# BOOST.net
KiCad netlist of a schematic drawn in Altium Designer
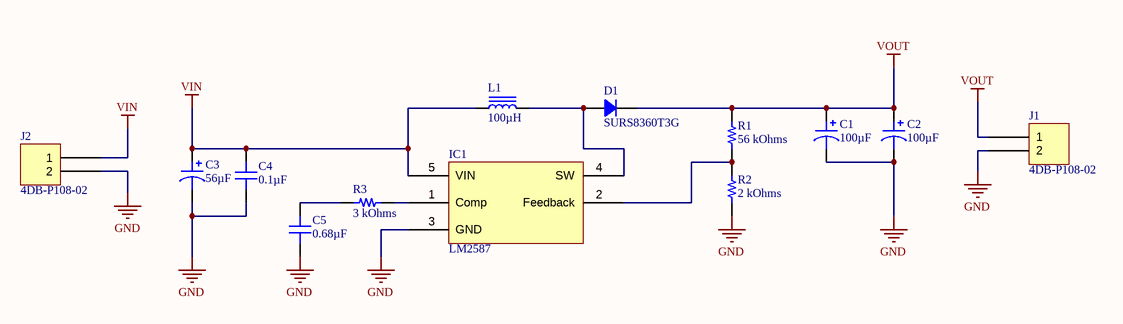
[diagram p0: BOOST.SchDoc]

(export (version "E")
  (design (tool "Eeschema 10.0.6"))
  (components
    (comp (ref "C1")
      (value "100µF")
      (footprint "CAP ALSMD 8.3MM H10.5MM")
      (description "CAP ALUM 100UF 20% 50V SMD")
      (fields
        (field (name "PART NUMBER") "EEE-FK1H101P")
        (field (name "MANUFACTURER") "Panasonic Electronic Components")
      )
      (libsource (lib "Celestial Altium Library - altium_library") (part "Polarised Capacitor"))
    )
    (comp (ref "C2")
      (value "100µF")
      (footprint "CAP ALSMD 8.3MM H10.5MM")
      (description "CAP ALUM 100UF 20% 50V SMD")
      (fields
        (field (name "PART NUMBER") "EEE-FK1H101P")
        (field (name "MANUFACTURER") "Panasonic Electronic Components")
      )
      (libsource (lib "Celestial Altium Library - altium_library") (part "Polarised Capacitor"))
    )
    (comp (ref "C3")
      (value "56µF")
      (footprint "CAP ALSMD 6.6MM H7.7MM")
      (description "CAP ALUM 56UF 20% 35V SMD")
      (fields (field (name "PART NUMBER") "UWD1V560MCL1GS") (field (name "MANUFACTURER") "Nichicon"))
      (libsource (lib "Celestial Altium Library - altium_library") (part "Polarised Capacitor"))
    )
    (comp (ref "C4")
      (value "0.1µF")
      (footprint "CAP 0805_2012")
      (description "CAP CER 0.1UF 50V X7R 0805")
      (fields (field (name "PART NUMBER") "CC0805JRX7R9BB104") (field (name "MANUFACTURER") "Yageo"))
      (libsource (lib "Celestial Altium Library - altium_library") (part "Capacitor"))
    )
    (comp (ref "C5")
      (value "0.68µF")
      (footprint "CAP 0805_2012")
      (description "CAP CER 0.68UF 50V X7R 0805")
      (fields (field (name "PART NUMBER") "C0805C684K5RACTU") (field (name "MANUFACTURER") "KEMET"))
      (libsource (lib "Celestial Altium Library - altium_library") (part "Capacitor"))
    )
    (comp (ref "D1")
      (value "SURS8360T3G")
      (footprint "DO214AB SMC")
      (description "DIODE GEN PURP 600V 3A SMC")
      (fields (field (name "MANUFACTURER") "ON Semiconductor"))
      (libsource (lib "Celestial Altium Library - altium_library") (part "Diode"))
    )
    (comp (ref "IC1")
      (value "LM2587")
      (footprint "AltiumLive:D2PAK")
      (description "Boost Converter")
      (libsource (lib "AltiumLive") (part "LM2587"))
    )
    (comp (ref "J1")
      (value "4DB-P108-02")
      (footprint "TE 4DB-P108-02")
      (description "CONN BARRIER STRIP 2CIRC 0.325\"")
      (fields (field (name "MANUFACTURER") "TE Connectivity AMP Connectors"))
      (libsource (lib "") (part "2 Pin_1"))
    )
    (comp (ref "J2")
      (value "4DB-P108-02")
      (footprint "TE 4DB-P108-02")
      (description "CONN BARRIER STRIP 2CIRC 0.325\"")
      (fields (field (name "MANUFACTURER") "TE Connectivity AMP Connectors"))
      (libsource (lib "Celestial Altium Library - altium_library") (part "2 Pin"))
    )
    (comp (ref "L1")
      (value "100µH")
      (footprint "AltiumLive:7447070")
      (description "FIXED IND 100UH 2.1A 150MOHM SMD")
      (fields (field (name "PART NUMBER") "SRR1280-101M") (field (name "MANUFACTURER") "Bourns Inc."))
      (libsource (lib "Celestial Altium Library - altium_library") (part "Inductor"))
    )
    (comp (ref "R1")
      (value "56 kOhms")
      (footprint "RES 0805_2012")
      (description "RES 56K OHM 1% 1/8W 0805")
      (fields
        (field (name "PART NUMBER") "RMCF0805FT56K0")
        (field (name "MANUFACTURER") "Stackpole Electronics Inc")
      )
      (libsource (lib "Celestial Altium Library - altium_library") (part "Resistor"))
    )
    (comp (ref "R2")
      (value "2 kOhms")
      (footprint "RES 0805_2012")
      (description "RES SMD 2K OHM 1% 1/8W 0805")
      (fields (field (name "PART NUMBER") "AC0805FR-072KL") (field (name "MANUFACTURER") "Yageo"))
      (libsource (lib "Celestial Altium Library - altium_library") (part "Resistor"))
    )
    (comp (ref "R3")
      (value "3 kOhms")
      (footprint "RES 0805_2012")
      (description "RES SMD 3K OHM 1% 1/8W 0805")
      (fields
        (field (name "PART NUMBER") "ERJ-6ENF3001V")
        (field (name "MANUFACTURER") "Panasonic Electronic Components")
      )
      (libsource (lib "Celestial Altium Library - altium_library") (part "Resistor"))
    )
  )
  (nets
    (net (code "1") (name "GND") (class "Default")
      (node (ref "C1") (pin "2") (pinfunction "2_2") (pintype "passive"))
      (node (ref "C2") (pin "2") (pinfunction "2_2") (pintype "passive"))
      (node (ref "C3") (pin "2") (pinfunction "2_2") (pintype "passive"))
      (node (ref "C4") (pin "1") (pinfunction "1_1") (pintype "passive"))
      (node (ref "C5") (pin "1") (pinfunction "1_1") (pintype "passive"))
      (node (ref "IC1") (pin "3") (pinfunction "GND_3") (pintype "passive"))
      (node (ref "J1") (pin "2") (pinfunction "2_2") (pintype "passive"))
      (node (ref "J2") (pin "2") (pinfunction "2_2") (pintype "passive"))
      (node (ref "R2") (pin "1") (pinfunction "1_1") (pintype "passive"))
    )
    (net (code "2") (name "Net-(C5-Pad2)") (class "Default")
      (node (ref "C5") (pin "2") (pinfunction "2_2") (pintype "passive"))
      (node (ref "R3") (pin "2") (pinfunction "2_2") (pintype "passive"))
    )
    (net (code "3") (name "Net-(IC1-Comp)") (class "Default")
      (node (ref "IC1") (pin "1") (pinfunction "Comp_1") (pintype "passive"))
      (node (ref "R3") (pin "1") (pinfunction "1_1") (pintype "passive"))
    )
    (net (code "4") (name "Net-(IC1-Feedback)") (class "Default")
      (node (ref "IC1") (pin "2") (pinfunction "Feedback_2") (pintype "passive"))
      (node (ref "R1") (pin "1") (pinfunction "1_1") (pintype "passive"))
      (node (ref "R2") (pin "2") (pinfunction "2_2") (pintype "passive"))
    )
    (net (code "5") (name "Net-(IC1-SW)") (class "Default")
      (node (ref "D1") (pin "1") (pinfunction "1_1") (pintype "passive"))
      (node (ref "IC1") (pin "4") (pinfunction "SW_4") (pintype "passive"))
      (node (ref "L1") (pin "2") (pinfunction "2_2") (pintype "passive"))
    )
    (net (code "6") (name "VIN") (class "Default")
      (node (ref "C3") (pin "1") (pinfunction "1_1") (pintype "passive"))
      (node (ref "C4") (pin "2") (pinfunction "2_2") (pintype "passive"))
      (node (ref "IC1") (pin "5") (pinfunction "VIN_5") (pintype "passive"))
      (node (ref "J2") (pin "1") (pinfunction "1_1") (pintype "passive"))
      (node (ref "L1") (pin "1") (pinfunction "1_1") (pintype "passive"))
    )
    (net (code "7") (name "VOUT") (class "Default")
      (node (ref "C1") (pin "1") (pinfunction "1_1") (pintype "passive"))
      (node (ref "C2") (pin "1") (pinfunction "1_1") (pintype "passive"))
      (node (ref "D1") (pin "2") (pinfunction "2_2") (pintype "passive"))
      (node (ref "J1") (pin "1") (pinfunction "1_1") (pintype "passive"))
      (node (ref "R1") (pin "2") (pinfunction "2_2") (pintype "passive"))
    )
  )
)
